# MICROCONTROLLER_ATMEGA-128L.net
KiCad netlist of a schematic drawn in EAGLE
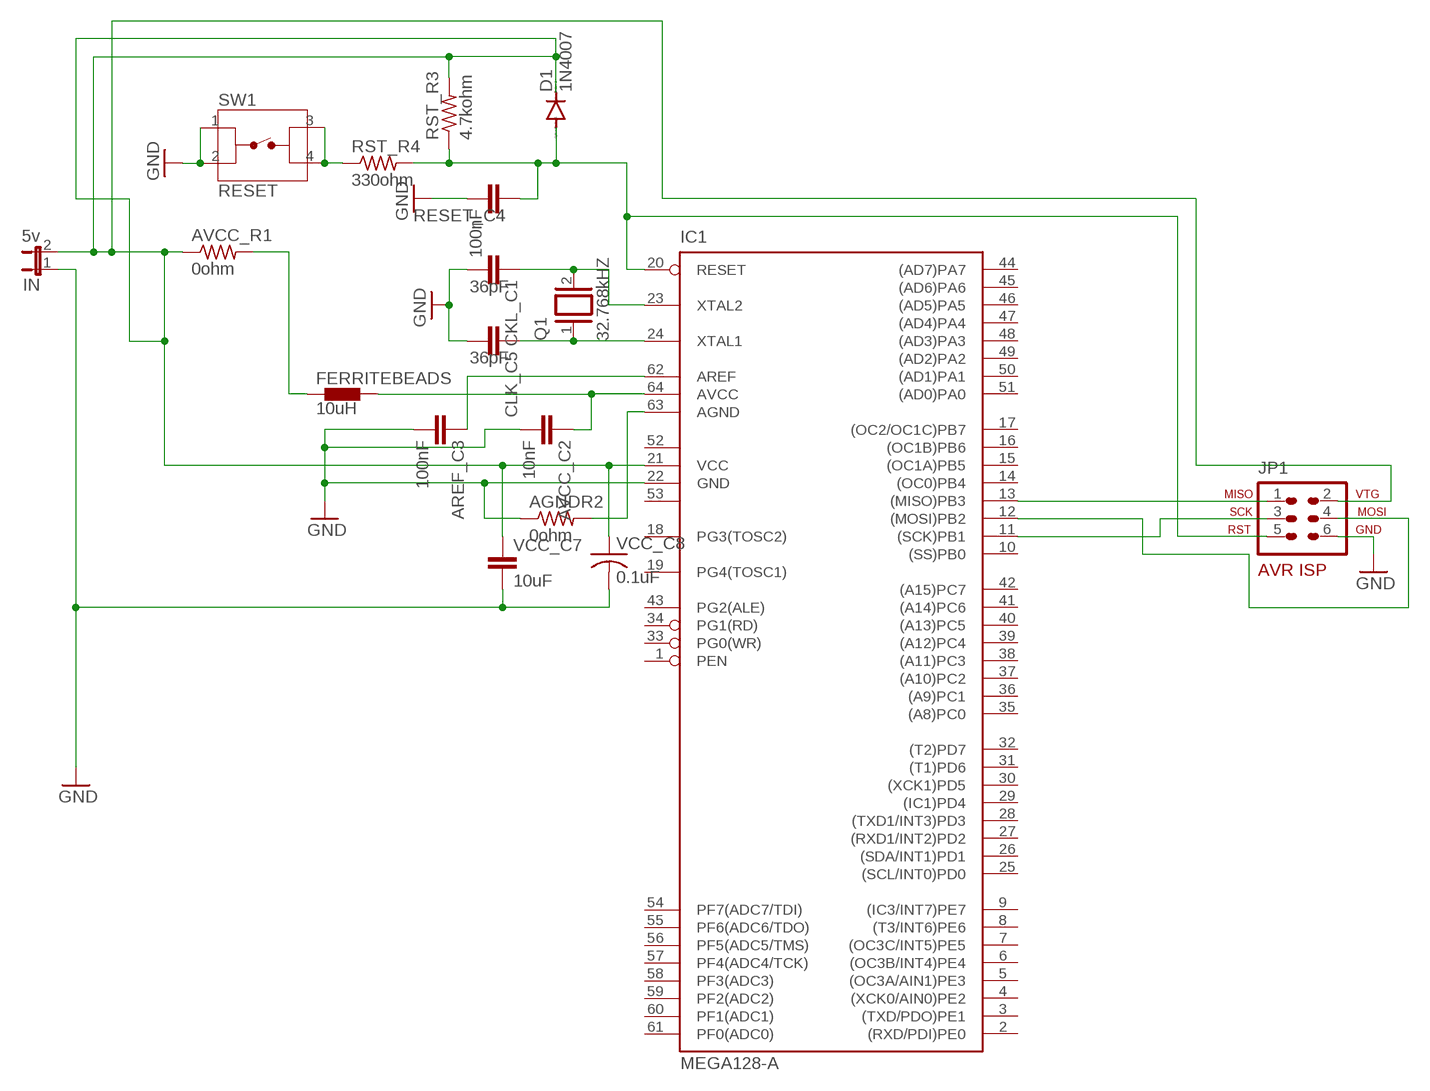
[diagram p0: schematic, sheet 1]

(export (version "E")
  (design (tool "Eeschema 10.0.6"))
  (components
    (comp (ref "AGNDR2")
      (value "0ohm")
      (footprint "eagle-import:0204_5")
      (libsource (lib "eagle-import") (part "R-US_0204/5"))
    )
    (comp (ref "AREF_C3")
      (value "100nF")
      (footprint "eagle-import:C5B3")
      (libsource (lib "eagle-import") (part "C5/3"))
    )
    (comp (ref "AVCC_C2")
      (value "10nF")
      (footprint "eagle-import:C5B3")
      (libsource (lib "eagle-import") (part "C5/3"))
    )
    (comp (ref "AVCC_R1")
      (value "0ohm")
      (footprint "eagle-import:0204_5")
      (libsource (lib "eagle-import") (part "R-US_0204/5"))
    )
    (comp (ref "CKL_C1")
      (value "36pF")
      (footprint "eagle-import:C5B3")
      (libsource (lib "eagle-import") (part "C5/3"))
    )
    (comp (ref "CLK_C5")
      (value "36pF")
      (footprint "eagle-import:C5B3")
      (libsource (lib "eagle-import") (part "C5/3"))
    )
    (comp (ref "D1")
      (value "1N4007")
      (footprint "eagle-import:DO41-10")
      (libsource (lib "eagle-import") (part "1N4004"))
    )
    (comp (ref "FERRITEBEADS")
      (value "10uH")
      (footprint "eagle-import:0402")
      (libsource (lib "eagle-import") (part "BLM15HB221SN1"))
    )
    (comp (ref "IC1")
      (value "MEGA128-A")
      (footprint "eagle-import:TQFP64")
      (libsource (lib "eagle-import") (part "MEGA128-A"))
    )
    (comp (ref "IN")
      (value "5v")
      (footprint "eagle-import:JP1")
      (libsource (lib "eagle-import") (part "JP1E"))
    )
    (comp (ref "JP1")
      (value "AVR-ISP-6R")
      (footprint "eagle-import:AVR-ISP-6R")
      (libsource (lib "eagle-import") (part "AVR-ISP-6R"))
    )
    (comp (ref "Q1")
      (value "32.768kHZ")
      (footprint "eagle-import:QS")
      (libsource (lib "eagle-import") (part "XTAL/S"))
    )
    (comp (ref "RESET_C4")
      (value "100nF")
      (footprint "eagle-import:C5B3")
      (libsource (lib "eagle-import") (part "C5/3"))
    )
    (comp (ref "RST_R3")
      (value "4.7kohm")
      (footprint "eagle-import:0204_5")
      (libsource (lib "eagle-import") (part "R-US_0204/5"))
    )
    (comp (ref "RST_R4")
      (value "330ohm")
      (footprint "eagle-import:0204_5")
      (libsource (lib "eagle-import") (part "R-US_0204/5"))
    )
    (comp (ref "SW1")
      (value "RESET")
      (footprint "eagle-import:TE_FSM4JSMA")
      (fields
        (field (name "COMMENT") "4-1437565-1")
        (field (name "MF") "TE Connectivity")
        (field (name "MP") "FSM4JSMA")
      )
      (libsource (lib "eagle-import") (part "FSM4JSMA"))
    )
    (comp (ref "VCC_C7")
      (value "10uF")
      (footprint "eagle-import:C5B3")
      (libsource (lib "eagle-import") (part "C5/3"))
    )
    (comp (ref "VCC_C8")
      (value "0.1uF")
      (footprint "eagle-import:C0603K")
      (libsource (lib "eagle-import") (part "C-USC0603K"))
    )
  )
  (nets
    (net (code "1") (name "/GND1") (class "Default")
      (node (ref "IC1") (pin "53") (pinfunction "GND1_53") (pintype "power_in"))
    )
    (net (code "2") (name "/VCC1") (class "Default")
      (node (ref "IC1") (pin "52") (pinfunction "VCC1_52") (pintype "power_in"))
    )
    (net (code "3") (name "GND") (class "Default")
      (node (ref "AGNDR2") (pin "1") (pinfunction "1_1") (pintype "passive"))
      (node (ref "AREF_C3") (pin "2") (pinfunction "2_2") (pintype "passive"))
      (node (ref "AVCC_C2") (pin "2") (pinfunction "2_2") (pintype "passive"))
      (node (ref "CKL_C1") (pin "2") (pinfunction "2_2") (pintype "passive"))
      (node (ref "CLK_C5") (pin "2") (pinfunction "2_2") (pintype "passive"))
      (node (ref "IC1") (pin "22") (pinfunction "GND_22") (pintype "power_in"))
      (node (ref "IN") (pin "1") (pinfunction "1_1") (pintype "passive"))
      (node (ref "JP1") (pin "6") (pinfunction "6_6") (pintype "passive"))
      (node (ref "RESET_C4") (pin "2") (pinfunction "2_2") (pintype "passive"))
      (node (ref "SW1") (pin "1") (pinfunction "1_1") (pintype "passive"))
      (node (ref "SW1") (pin "2") (pinfunction "2_2") (pintype "passive"))
      (node (ref "VCC_C7") (pin "2") (pinfunction "2_2") (pintype "passive"))
      (node (ref "VCC_C8") (pin "2") (pinfunction "2_2") (pintype "passive"))
    )
    (net (code "4") (name "Net-(AVCC_R1-Pad2)") (class "Default")
      (node (ref "AVCC_R1") (pin "2") (pinfunction "2_2") (pintype "passive"))
      (node (ref "FERRITEBEADS") (pin "1") (pinfunction "1_1") (pintype "passive"))
    )
    (net (code "5") (name "Net-(IC1-(MISO)PB3)") (class "Default")
      (node (ref "IC1") (pin "13") (pinfunction "(MISO)PB3_13") (pintype "bidirectional"))
      (node (ref "JP1") (pin "1") (pinfunction "1_1") (pintype "passive"))
    )
    (net (code "6") (name "Net-(IC1-(MOSI)PB2)") (class "Default")
      (node (ref "IC1") (pin "12") (pinfunction "(MOSI)PB2_12") (pintype "bidirectional"))
      (node (ref "JP1") (pin "4") (pinfunction "4_4") (pintype "passive"))
    )
    (net (code "7") (name "Net-(IC1-(SCK)PB1)") (class "Default")
      (node (ref "IC1") (pin "11") (pinfunction "(SCK)PB1_11") (pintype "bidirectional"))
      (node (ref "JP1") (pin "3") (pinfunction "3_3") (pintype "passive"))
    )
    (net (code "8") (name "Net-(IC1-AGND)") (class "Default")
      (node (ref "AGNDR2") (pin "2") (pinfunction "2_2") (pintype "passive"))
      (node (ref "IC1") (pin "63") (pinfunction "AGND_63") (pintype "power_in"))
    )
    (net (code "9") (name "Net-(IC1-AREF)") (class "Default")
      (node (ref "AREF_C3") (pin "1") (pinfunction "1_1") (pintype "passive"))
      (node (ref "IC1") (pin "62") (pinfunction "AREF_62") (pintype "passive"))
    )
    (net (code "10") (name "Net-(IC1-AVCC)") (class "Default")
      (node (ref "AVCC_C2") (pin "1") (pinfunction "1_1") (pintype "passive"))
      (node (ref "FERRITEBEADS") (pin "2") (pinfunction "2_2") (pintype "passive"))
      (node (ref "IC1") (pin "64") (pinfunction "AVCC_64") (pintype "power_in"))
    )
    (net (code "11") (name "Net-(IC1-RESET)") (class "Default")
      (node (ref "D1") (pin "A") (pinfunction "A_A") (pintype "passive"))
      (node (ref "IC1") (pin "20") (pinfunction "RESET_20") (pintype "input"))
      (node (ref "JP1") (pin "5") (pinfunction "5_5") (pintype "passive"))
      (node (ref "RESET_C4") (pin "1") (pinfunction "1_1") (pintype "passive"))
      (node (ref "RST_R3") (pin "1") (pinfunction "1_1") (pintype "passive"))
      (node (ref "RST_R4") (pin "2") (pinfunction "2_2") (pintype "passive"))
    )
    (net (code "12") (name "Net-(IC1-VCC)") (class "Default")
      (node (ref "AVCC_R1") (pin "1") (pinfunction "1_1") (pintype "passive"))
      (node (ref "D1") (pin "C") (pinfunction "C_C") (pintype "passive"))
      (node (ref "IC1") (pin "21") (pinfunction "VCC_21") (pintype "power_in"))
      (node (ref "IN") (pin "2") (pinfunction "2_2") (pintype "passive"))
      (node (ref "JP1") (pin "2") (pinfunction "2_2") (pintype "passive"))
      (node (ref "RST_R3") (pin "2") (pinfunction "2_2") (pintype "passive"))
      (node (ref "VCC_C7") (pin "1") (pinfunction "1_1") (pintype "passive"))
      (node (ref "VCC_C8") (pin "1") (pinfunction "1_1") (pintype "passive"))
    )
    (net (code "13") (name "Net-(IC1-XTAL1)") (class "Default")
      (node (ref "CLK_C5") (pin "1") (pinfunction "1_1") (pintype "passive"))
      (node (ref "IC1") (pin "24") (pinfunction "XTAL1_24") (pintype "bidirectional"))
      (node (ref "Q1") (pin "1") (pinfunction "1_1") (pintype "passive"))
    )
    (net (code "14") (name "Net-(IC1-XTAL2)") (class "Default")
      (node (ref "CKL_C1") (pin "1") (pinfunction "1_1") (pintype "passive"))
      (node (ref "IC1") (pin "23") (pinfunction "XTAL2_23") (pintype "bidirectional"))
      (node (ref "Q1") (pin "2") (pinfunction "2_2") (pintype "passive"))
    )
    (net (code "15") (name "Net-(RST_R4-Pad1)") (class "Default")
      (node (ref "RST_R4") (pin "1") (pinfunction "1_1") (pintype "passive"))
      (node (ref "SW1") (pin "3") (pinfunction "3_3") (pintype "passive"))
      (node (ref "SW1") (pin "4") (pinfunction "4_4") (pintype "passive"))
    )
    (net (code "16") (name "unconnected-(IC1-(A8)PC0-Pad35)") (class "Default")
      (node (ref "IC1") (pin "35") (pinfunction "(A8)PC0_35") (pintype "output"))
    )
    (net (code "17") (name "unconnected-(IC1-(A9)PC1-Pad36)") (class "Default")
      (node (ref "IC1") (pin "36") (pinfunction "(A9)PC1_36") (pintype "output"))
    )
    (net (code "18") (name "unconnected-(IC1-(A10)PC2-Pad37)") (class "Default")
      (node (ref "IC1") (pin "37") (pinfunction "(A10)PC2_37") (pintype "output"))
    )
    (net (code "19") (name "unconnected-(IC1-(A11)PC3-Pad38)") (class "Default")
      (node (ref "IC1") (pin "38") (pinfunction "(A11)PC3_38") (pintype "output"))
    )
    (net (code "20") (name "unconnected-(IC1-(A12)PC4-Pad39)") (class "Default")
      (node (ref "IC1") (pin "39") (pinfunction "(A12)PC4_39") (pintype "output"))
    )
    (net (code "21") (name "unconnected-(IC1-(A13)PC5-Pad40)") (class "Default")
      (node (ref "IC1") (pin "40") (pinfunction "(A13)PC5_40") (pintype "output"))
    )
    (net (code "22") (name "unconnected-(IC1-(A14)PC6-Pad41)") (class "Default")
      (node (ref "IC1") (pin "41") (pinfunction "(A14)PC6_41") (pintype "output"))
    )
    (net (code "23") (name "unconnected-(IC1-(A15)PC7-Pad42)") (class "Default")
      (node (ref "IC1") (pin "42") (pinfunction "(A15)PC7_42") (pintype "output"))
    )
    (net (code "24") (name "unconnected-(IC1-(AD0)PA0-Pad51)") (class "Default")
      (node (ref "IC1") (pin "51") (pinfunction "(AD0)PA0_51") (pintype "bidirectional"))
    )
    (net (code "25") (name "unconnected-(IC1-(AD1)PA1-Pad50)") (class "Default")
      (node (ref "IC1") (pin "50") (pinfunction "(AD1)PA1_50") (pintype "bidirectional"))
    )
    (net (code "26") (name "unconnected-(IC1-(AD2)PA2-Pad49)") (class "Default")
      (node (ref "IC1") (pin "49") (pinfunction "(AD2)PA2_49") (pintype "bidirectional"))
    )
    (net (code "27") (name "unconnected-(IC1-(AD3)PA3-Pad48)") (class "Default")
      (node (ref "IC1") (pin "48") (pinfunction "(AD3)PA3_48") (pintype "bidirectional"))
    )
    (net (code "28") (name "unconnected-(IC1-(AD4)PA4-Pad47)") (class "Default")
      (node (ref "IC1") (pin "47") (pinfunction "(AD4)PA4_47") (pintype "bidirectional"))
    )
    (net (code "29") (name "unconnected-(IC1-(AD5)PA5-Pad46)") (class "Default")
      (node (ref "IC1") (pin "46") (pinfunction "(AD5)PA5_46") (pintype "bidirectional"))
    )
    (net (code "30") (name "unconnected-(IC1-(AD6)PA6-Pad45)") (class "Default")
      (node (ref "IC1") (pin "45") (pinfunction "(AD6)PA6_45") (pintype "bidirectional"))
    )
    (net (code "31") (name "unconnected-(IC1-(AD7)PA7-Pad44)") (class "Default")
      (node (ref "IC1") (pin "44") (pinfunction "(AD7)PA7_44") (pintype "bidirectional"))
    )
    (net (code "32") (name "unconnected-(IC1-(IC1)PD4-Pad29)") (class "Default")
      (node (ref "IC1") (pin "29") (pinfunction "(IC1)PD4_29") (pintype "bidirectional"))
    )
    (net (code "33") (name "unconnected-(IC1-(IC3{slash}INT7)PE7-Pad9)") (class "Default")
      (node (ref "IC1") (pin "9") (pinfunction "(IC3/INT7)PE7_9") (pintype "bidirectional"))
    )
    (net (code "34") (name "unconnected-(IC1-(OC0)PB4-Pad14)") (class "Default")
      (node (ref "IC1") (pin "14") (pinfunction "(OC0)PB4_14") (pintype "bidirectional"))
    )
    (net (code "35") (name "unconnected-(IC1-(OC1A)PB5-Pad15)") (class "Default")
      (node (ref "IC1") (pin "15") (pinfunction "(OC1A)PB5_15") (pintype "bidirectional"))
    )
    (net (code "36") (name "unconnected-(IC1-(OC1B)PB6-Pad16)") (class "Default")
      (node (ref "IC1") (pin "16") (pinfunction "(OC1B)PB6_16") (pintype "bidirectional"))
    )
    (net (code "37") (name "unconnected-(IC1-(OC2{slash}OC1C)PB7-Pad17)") (class "Default")
      (node (ref "IC1") (pin "17") (pinfunction "(OC2/OC1C)PB7_17") (pintype "bidirectional"))
    )
    (net (code "38") (name "unconnected-(IC1-(OC3A{slash}AIN1)PE3-Pad5)") (class "Default")
      (node (ref "IC1") (pin "5") (pinfunction "(OC3A/AIN1)PE3_5") (pintype "bidirectional"))
    )
    (net (code "39") (name "unconnected-(IC1-(OC3B{slash}INT4)PE4-Pad6)") (class "Default")
      (node (ref "IC1") (pin "6") (pinfunction "(OC3B/INT4)PE4_6") (pintype "bidirectional"))
    )
    (net (code "40") (name "unconnected-(IC1-(OC3C{slash}INT5)PE5-Pad7)") (class "Default")
      (node (ref "IC1") (pin "7") (pinfunction "(OC3C/INT5)PE5_7") (pintype "bidirectional"))
    )
    (net (code "41") (name "unconnected-(IC1-(RXD1{slash}INT2)PD2-Pad27)") (class "Default")
      (node (ref "IC1") (pin "27") (pinfunction "(RXD1/INT2)PD2_27") (pintype "bidirectional"))
    )
    (net (code "42") (name "unconnected-(IC1-(RXD{slash}PDI)PE0-Pad2)") (class "Default")
      (node (ref "IC1") (pin "2") (pinfunction "(RXD/PDI)PE0_2") (pintype "bidirectional"))
    )
    (net (code "43") (name "unconnected-(IC1-(SCL{slash}INT0)PD0-Pad25)") (class "Default")
      (node (ref "IC1") (pin "25") (pinfunction "(SCL/INT0)PD0_25") (pintype "bidirectional"))
    )
    (net (code "44") (name "unconnected-(IC1-(SDA{slash}INT1)PD1-Pad26)") (class "Default")
      (node (ref "IC1") (pin "26") (pinfunction "(SDA/INT1)PD1_26") (pintype "bidirectional"))
    )
    (net (code "45") (name "unconnected-(IC1-(SS)PB0-Pad10)") (class "Default")
      (node (ref "IC1") (pin "10") (pinfunction "(SS)PB0_10") (pintype "bidirectional"))
    )
    (net (code "46") (name "unconnected-(IC1-(T1)PD6-Pad31)") (class "Default")
      (node (ref "IC1") (pin "31") (pinfunction "(T1)PD6_31") (pintype "bidirectional"))
    )
    (net (code "47") (name "unconnected-(IC1-(T2)PD7-Pad32)") (class "Default")
      (node (ref "IC1") (pin "32") (pinfunction "(T2)PD7_32") (pintype "bidirectional"))
    )
    (net (code "48") (name "unconnected-(IC1-(T3{slash}INT6)PE6-Pad8)") (class "Default")
      (node (ref "IC1") (pin "8") (pinfunction "(T3/INT6)PE6_8") (pintype "bidirectional"))
    )
    (net (code "49") (name "unconnected-(IC1-(TXD1{slash}INT3)PD3-Pad28)") (class "Default")
      (node (ref "IC1") (pin "28") (pinfunction "(TXD1/INT3)PD3_28") (pintype "bidirectional"))
    )
    (net (code "50") (name "unconnected-(IC1-(TXD{slash}PDO)PE1-Pad3)") (class "Default")
      (node (ref "IC1") (pin "3") (pinfunction "(TXD/PDO)PE1_3") (pintype "bidirectional"))
    )
    (net (code "51") (name "unconnected-(IC1-(XCK0{slash}AIN0)PE2-Pad4)") (class "Default")
      (node (ref "IC1") (pin "4") (pinfunction "(XCK0/AIN0)PE2_4") (pintype "bidirectional"))
    )
    (net (code "52") (name "unconnected-(IC1-(XCK1)PD5-Pad30)") (class "Default")
      (node (ref "IC1") (pin "30") (pinfunction "(XCK1)PD5_30") (pintype "bidirectional"))
    )
    (net (code "53") (name "unconnected-(IC1-PEN-Pad1)") (class "Default")
      (node (ref "IC1") (pin "1") (pinfunction "PEN_1") (pintype "input"))
    )
    (net (code "54") (name "unconnected-(IC1-PF0(ADC0)-Pad61)") (class "Default")
      (node (ref "IC1") (pin "61") (pinfunction "PF0(ADC0)_61") (pintype "input"))
    )
    (net (code "55") (name "unconnected-(IC1-PF1(ADC1)-Pad60)") (class "Default")
      (node (ref "IC1") (pin "60") (pinfunction "PF1(ADC1)_60") (pintype "input"))
    )
    (net (code "56") (name "unconnected-(IC1-PF2(ADC2)-Pad59)") (class "Default")
      (node (ref "IC1") (pin "59") (pinfunction "PF2(ADC2)_59") (pintype "input"))
    )
    (net (code "57") (name "unconnected-(IC1-PF3(ADC3)-Pad58)") (class "Default")
      (node (ref "IC1") (pin "58") (pinfunction "PF3(ADC3)_58") (pintype "input"))
    )
    (net (code "58") (name "unconnected-(IC1-PF4(ADC4{slash}TCK)-Pad57)") (class "Default")
      (node (ref "IC1") (pin "57") (pinfunction "PF4(ADC4/TCK)_57") (pintype "input"))
    )
    (net (code "59") (name "unconnected-(IC1-PF5(ADC5{slash}TMS)-Pad56)") (class "Default")
      (node (ref "IC1") (pin "56") (pinfunction "PF5(ADC5/TMS)_56") (pintype "input"))
    )
    (net (code "60") (name "unconnected-(IC1-PF6(ADC6{slash}TDO)-Pad55)") (class "Default")
      (node (ref "IC1") (pin "55") (pinfunction "PF6(ADC6/TDO)_55") (pintype "input"))
    )
    (net (code "61") (name "unconnected-(IC1-PF7(ADC7{slash}TDI)-Pad54)") (class "Default")
      (node (ref "IC1") (pin "54") (pinfunction "PF7(ADC7/TDI)_54") (pintype "input"))
    )
    (net (code "62") (name "unconnected-(IC1-PG0(WR)-Pad33)") (class "Default")
      (node (ref "IC1") (pin "33") (pinfunction "PG0(WR)_33") (pintype "bidirectional"))
    )
    (net (code "63") (name "unconnected-(IC1-PG1(RD)-Pad34)") (class "Default")
      (node (ref "IC1") (pin "34") (pinfunction "PG1(RD)_34") (pintype "bidirectional"))
    )
    (net (code "64") (name "unconnected-(IC1-PG2(ALE)-Pad43)") (class "Default")
      (node (ref "IC1") (pin "43") (pinfunction "PG2(ALE)_43") (pintype "bidirectional"))
    )
    (net (code "65") (name "unconnected-(IC1-PG3(TOSC2)-Pad18)") (class "Default")
      (node (ref "IC1") (pin "18") (pinfunction "PG3(TOSC2)_18") (pintype "bidirectional"))
    )
    (net (code "66") (name "unconnected-(IC1-PG4(TOSC1)-Pad19)") (class "Default")
      (node (ref "IC1") (pin "19") (pinfunction "PG4(TOSC1)_19") (pintype "bidirectional"))
    )
  )
)
